# FPGA_Config_Power.net
KiCad netlist of a schematic drawn in Altium Designer
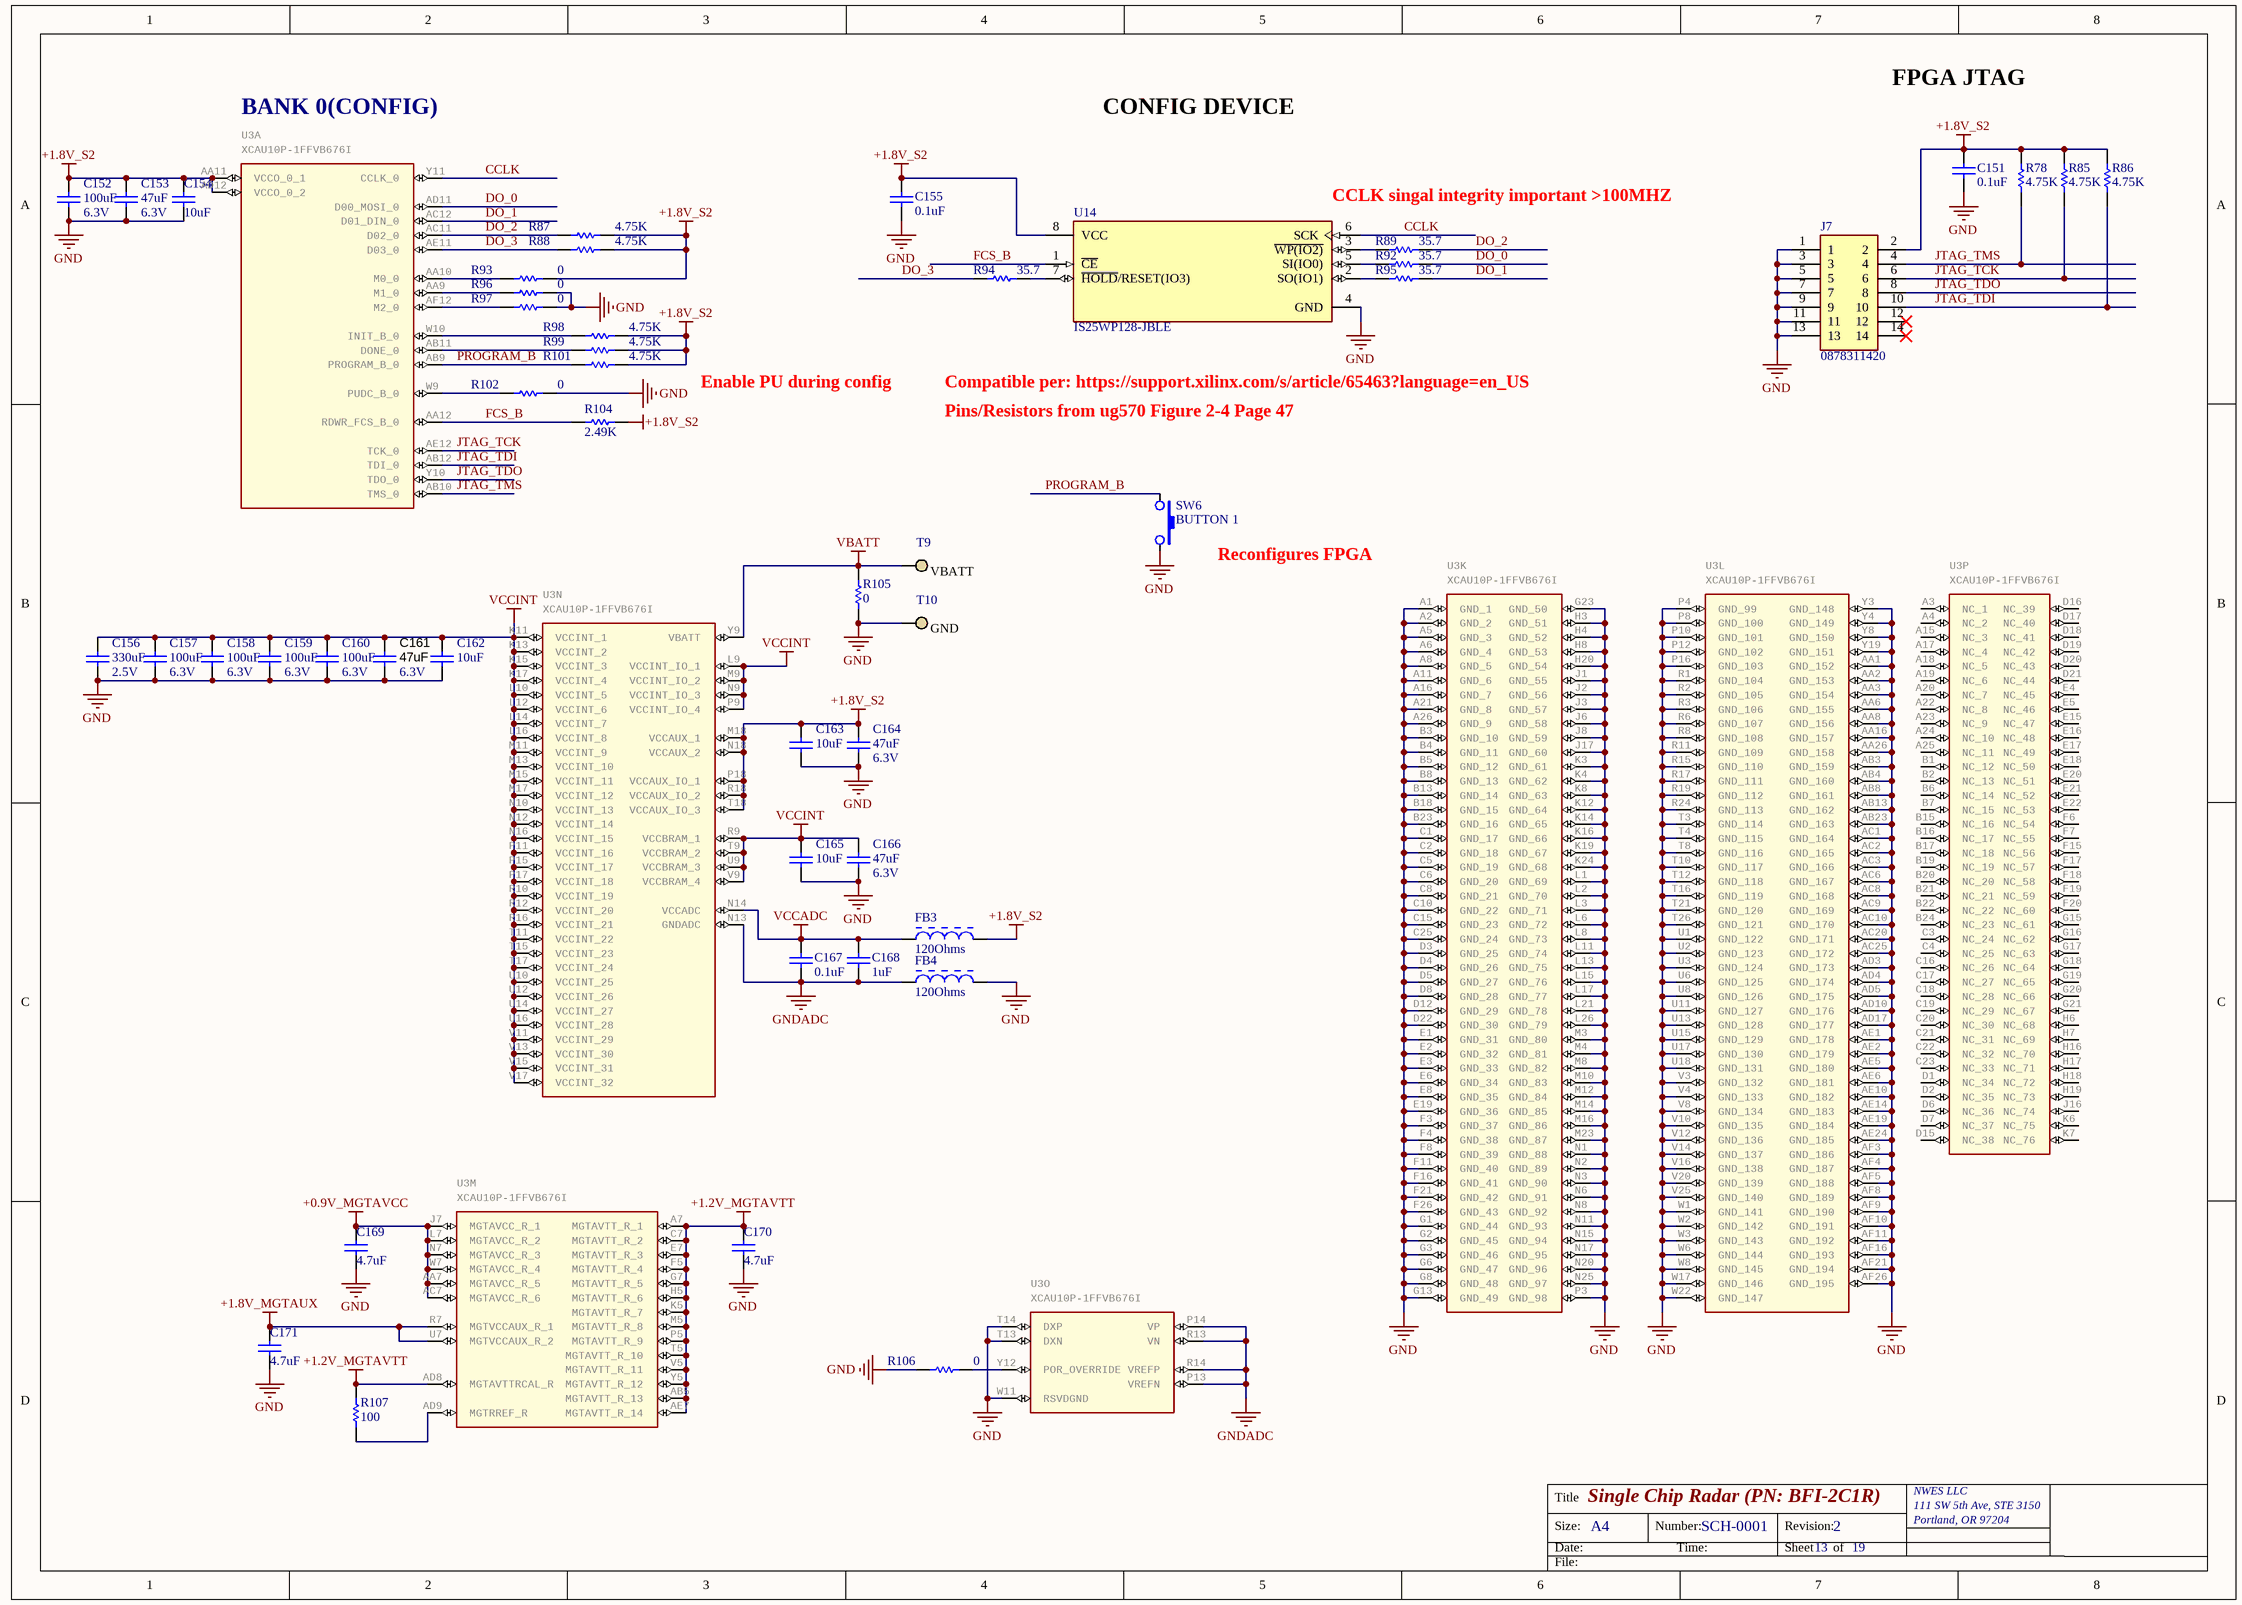
[diagram p0: FPGA Config_Power.SchDoc]

(export (version "E")
  (design (tool "Eeschema 10.0.6"))
  (components
    (comp (ref "C151")
      (value "0.1uF")
      (footprint "CAPC1005X55USR")
      (description "CAP CER 0.1UF 25V X5R 0402")
      (fields
        (field (name "MANUFACTURER PART NUMBER") "CL05A104KA5NNNC")
        (field (name "MANUFACTURER") "Samsung Electro-Mechanics")
      )
      (libsource (lib "Radar FPGA RF") (part "CAP CER 0.1UF 25V X5R 0402"))
    )
    (comp (ref "C152")
      (value "100uF")
      (footprint "CAPC2012X145USR")
      (description "0805 100 uF 6.3 V ±20% Tolerance X5R Multilayer Ceramic Chip Capacitor")
      (fields
        (field (name "MANUFACTURER") "Murata")
        (field (name "MANUFACTURER PART NUMBER") "GRM21BR60J107ME15L")
        (field (name "VOLTAGE RATING") "6.3V")
      )
      (libsource (lib "Radar FPGA RF") (part "CAP CER 100UF 6.3V X5R 0805"))
    )
    (comp (ref "C153")
      (value "47uF")
      (footprint "CAPC2012X145USR")
      (description "CAP CER 47UF 6.3V X5R 0805")
      (fields
        (field (name "MANUFACTURER") "Samsung")
        (field (name "MANUFACTURER PART NUMBER") "CL21A476MQYNNNE")
        (field (name "VOLTAGE RATING") "6.3V")
      )
      (libsource (lib "Radar FPGA RF") (part "CAP CER 47UF 6.3V X5R 0805"))
    )
    (comp (ref "C154")
      (value "10uF")
      (footprint "CAPC1005X90")
      (description "CAP CER 10UF 10V X5R 0402")
      (fields
        (field (name "MANUFACTURER PART NUMBER") "CL05A106MP8NUB8")
        (field (name "MANUFACTURER") "Samsung Electro-Mechanics")
      )
      (libsource (lib "Radar FPGA RF") (part "CAP CER 10UF 10V X5R 0402"))
    )
    (comp (ref "C155")
      (value "0.1uF")
      (footprint "CAPC1005X55USR")
      (description "CAP CER 0.1UF 25V X5R 0402")
      (fields
        (field (name "MANUFACTURER PART NUMBER") "CL05A104KA5NNNC")
        (field (name "MANUFACTURER") "Samsung Electro-Mechanics")
      )
      (libsource (lib "Radar FPGA RF") (part "CAP CER 0.1UF 25V X5R 0402"))
    )
    (comp (ref "C156")
      (value "330uF")
      (footprint "CAPC3225X280N")
      (description "1210 2.5V X6S 330uF 20% multilayer ceramic capacitor")
      (fields
        (field (name "MANUFACTURER") "Murata")
        (field (name "MANUFACTURER PART NUMBER") "GRM32EC80E337ME05L")
        (field (name "VOLTAGE RATING") "2.5V")
      )
      (libsource (lib "Radar FPGA RF") (part "CAP CER 330UF 2.5V X6S 1210"))
    )
    (comp (ref "C157")
      (value "100uF")
      (footprint "CAPC2012X145USR")
      (description "0805 100 uF 6.3 V ±20% Tolerance X5R Multilayer Ceramic Chip Capacitor")
      (fields
        (field (name "MANUFACTURER") "Murata")
        (field (name "MANUFACTURER PART NUMBER") "GRM21BR60J107ME15L")
        (field (name "VOLTAGE RATING") "6.3V")
      )
      (libsource (lib "Radar FPGA RF") (part "CAP CER 100UF 6.3V X5R 0805"))
    )
    (comp (ref "C158")
      (value "100uF")
      (footprint "CAPC2012X145USR")
      (description "0805 100 uF 6.3 V ±20% Tolerance X5R Multilayer Ceramic Chip Capacitor")
      (fields
        (field (name "MANUFACTURER") "Murata")
        (field (name "MANUFACTURER PART NUMBER") "GRM21BR60J107ME15L")
        (field (name "VOLTAGE RATING") "6.3V")
      )
      (libsource (lib "Radar FPGA RF") (part "CAP CER 100UF 6.3V X5R 0805"))
    )
    (comp (ref "C159")
      (value "100uF")
      (footprint "CAPC2012X145USR")
      (description "0805 100 uF 6.3 V ±20% Tolerance X5R Multilayer Ceramic Chip Capacitor")
      (fields
        (field (name "MANUFACTURER") "Murata")
        (field (name "MANUFACTURER PART NUMBER") "GRM21BR60J107ME15L")
        (field (name "VOLTAGE RATING") "6.3V")
      )
      (libsource (lib "Radar FPGA RF") (part "CAP CER 100UF 6.3V X5R 0805"))
    )
    (comp (ref "C160")
      (value "100uF")
      (footprint "CAPC2012X145USR")
      (description "0805 100 uF 6.3 V ±20% Tolerance X5R Multilayer Ceramic Chip Capacitor")
      (fields
        (field (name "MANUFACTURER") "Murata")
        (field (name "MANUFACTURER PART NUMBER") "GRM21BR60J107ME15L")
        (field (name "VOLTAGE RATING") "6.3V")
      )
      (libsource (lib "Radar FPGA RF") (part "CAP CER 100UF 6.3V X5R 0805"))
    )
    (comp (ref "C161")
      (value "47uF")
      (footprint "CAPC1608X100N")
      (description "0603 6.3 V 47 uF ±20% Tolerance X5R SMT Multilayer Ceramic Chp Capacitor")
      (fields
        (field (name "MANUFACTURER") "Murata")
        (field (name "MANUFACTURER PART NUMBER") "GRM188R60J476ME15D")
        (field (name "VOLTAGE RATING") "6.3V")
      )
      (libsource (lib "Radar FPGA RF") (part "CAP CER 47UF 6.3V X5R 0603"))
    )
    (comp (ref "C162")
      (value "10uF")
      (footprint "CAPC1005X90")
      (description "CAP CER 10UF 10V X5R 0402")
      (fields
        (field (name "MANUFACTURER PART NUMBER") "CL05A106MP8NUB8")
        (field (name "MANUFACTURER") "Samsung Electro-Mechanics")
      )
      (libsource (lib "Radar FPGA RF") (part "CAP CER 10UF 10V X5R 0402"))
    )
    (comp (ref "C163")
      (value "10uF")
      (footprint "CAPC1005X90")
      (description "CAP CER 10UF 10V X5R 0402")
      (fields
        (field (name "MANUFACTURER PART NUMBER") "CL05A106MP8NUB8")
        (field (name "MANUFACTURER") "Samsung Electro-Mechanics")
      )
      (libsource (lib "Radar FPGA RF") (part "CAP CER 10UF 10V X5R 0402"))
    )
    (comp (ref "C164")
      (value "47uF")
      (footprint "CAPC2012X145USR")
      (description "CAP CER 47UF 6.3V X5R 0805")
      (fields
        (field (name "MANUFACTURER") "Samsung")
        (field (name "MANUFACTURER PART NUMBER") "CL21A476MQYNNNE")
        (field (name "VOLTAGE RATING") "6.3V")
      )
      (libsource (lib "Radar FPGA RF") (part "CAP CER 47UF 6.3V X5R 0805"))
    )
    (comp (ref "C165")
      (value "10uF")
      (footprint "CAPC1005X90")
      (description "CAP CER 10UF 10V X5R 0402")
      (fields
        (field (name "MANUFACTURER PART NUMBER") "CL05A106MP8NUB8")
        (field (name "MANUFACTURER") "Samsung Electro-Mechanics")
      )
      (libsource (lib "Radar FPGA RF") (part "CAP CER 10UF 10V X5R 0402"))
    )
    (comp (ref "C166")
      (value "47uF")
      (footprint "CAPC2012X145USR")
      (description "CAP CER 47UF 6.3V X5R 0805")
      (fields
        (field (name "MANUFACTURER") "Samsung")
        (field (name "MANUFACTURER PART NUMBER") "CL21A476MQYNNNE")
        (field (name "VOLTAGE RATING") "6.3V")
      )
      (libsource (lib "Radar FPGA RF") (part "CAP CER 47UF 6.3V X5R 0805"))
    )
    (comp (ref "C167")
      (value "0.1uF")
      (footprint "CAPC1005X55USR")
      (description "CAP CER 0.1UF 25V X5R 0402")
      (fields
        (field (name "MANUFACTURER PART NUMBER") "CL05A104KA5NNNC")
        (field (name "MANUFACTURER") "Samsung Electro-Mechanics")
      )
      (libsource (lib "Radar FPGA RF") (part "CAP CER 0.1UF 25V X5R 0402"))
    )
    (comp (ref "C168")
      (value "1uF")
      (footprint "CAPC1005X55USR")
      (description "CAP CER 1UF 25V X5R 0402")
      (fields
        (field (name "MANUFACTURER PART NUMBER") "GRM155R61E105MA12D")
        (field (name "MANUFACTURER") "Murata Electronics")
      )
      (libsource (lib "Radar FPGA RF") (part "CAP CER 1UF 25V X5R 0402"))
    )
    (comp (ref "C169")
      (value "4.7uF")
      (footprint "CAPC1005X65USR")
      (description "CAP CER 4.7UF 10V X5R 0402")
      (fields
        (field (name "MANUFACTURER PART NUMBER") "C1005X5R1A475M050BC")
        (field (name "MANUFACTURER") "TDK Corporation")
      )
      (libsource (lib "Radar FPGA RF") (part "CAP CER 4.7UF 10V X5R 0402"))
    )
    (comp (ref "C170")
      (value "4.7uF")
      (footprint "CAPC1005X65USR")
      (description "CAP CER 4.7UF 10V X5R 0402")
      (fields
        (field (name "MANUFACTURER PART NUMBER") "C1005X5R1A475M050BC")
        (field (name "MANUFACTURER") "TDK Corporation")
      )
      (libsource (lib "Radar FPGA RF") (part "CAP CER 4.7UF 10V X5R 0402"))
    )
    (comp (ref "C171")
      (value "4.7uF")
      (footprint "CAPC1005X65USR")
      (description "CAP CER 4.7UF 10V X5R 0402")
      (fields
        (field (name "MANUFACTURER PART NUMBER") "C1005X5R1A475M050BC")
        (field (name "MANUFACTURER") "TDK Corporation")
      )
      (libsource (lib "Radar FPGA RF") (part "CAP CER 4.7UF 10V X5R 0402"))
    )
    (comp (ref "FB3")
      (value "120Ohms")
      (footprint "0402_FB")
      (description "FERRITE BEAD 120 OHM 0402 1LN")
      (fields
        (field (name "MANUFACTURER PART NUMBER") "BLM15AG121SN1D")
        (field (name "MANUFACTURER") "Murata Electronics")
      )
      (libsource (lib "Radar FPGA RF") (part "FERRITE BEAD 120 OHM 0402 1LN"))
    )
    (comp (ref "FB4")
      (value "120Ohms")
      (footprint "0402_FB")
      (description "FERRITE BEAD 120 OHM 0402 1LN")
      (fields
        (field (name "MANUFACTURER PART NUMBER") "BLM15AG121SN1D")
        (field (name "MANUFACTURER") "Murata Electronics")
      )
      (libsource (lib "Radar FPGA RF") (part "FERRITE BEAD 120 OHM 0402 1LN"))
    )
    (comp (ref "J7")
      (value "0878311420")
      (footprint "Molex_0878311420")
      (description "2.00mm Pitch Milli-Grid Header Vertical Through Hole Shrouded 14 Circuits 0.38")
      (fields (field (name "MANUFACTURER") "Molex") (field (name "MANUFACTURER PART NUMBER") "87831-1420"))
      (libsource (lib "Radar FPGA RF") (part "HEADER VERT 2X7 2MM"))
    )
    (comp (ref "R78")
      (value "4.75K")
      (footprint "RESC1005X40USR")
      (description "RES 4.75K OHM 1% 1/16W 0402")
      (fields
        (field (name "MANUFACTURER") "YAGEO")
        (field (name "MANUFACTURER PART NUMBER") "RC0402FR-074K75L")
      )
      (libsource (lib "Radar FPGA RF") (part "RES 4.75K OHM 1% 1/16W 0402"))
    )
    (comp (ref "R85")
      (value "4.75K")
      (footprint "RESC1005X40USR")
      (description "RES 4.75K OHM 1% 1/16W 0402")
      (fields
        (field (name "MANUFACTURER") "YAGEO")
        (field (name "MANUFACTURER PART NUMBER") "RC0402FR-074K75L")
      )
      (libsource (lib "Radar FPGA RF") (part "RES 4.75K OHM 1% 1/16W 0402"))
    )
    (comp (ref "R86")
      (value "4.75K")
      (footprint "RESC1005X40USR")
      (description "RES 4.75K OHM 1% 1/16W 0402")
      (fields
        (field (name "MANUFACTURER") "YAGEO")
        (field (name "MANUFACTURER PART NUMBER") "RC0402FR-074K75L")
      )
      (libsource (lib "Radar FPGA RF") (part "RES 4.75K OHM 1% 1/16W 0402"))
    )
    (comp (ref "R87")
      (value "4.75K")
      (footprint "RESC1005X40USR")
      (description "RES 4.75K OHM 1% 1/16W 0402")
      (fields
        (field (name "MANUFACTURER") "YAGEO")
        (field (name "MANUFACTURER PART NUMBER") "RC0402FR-074K75L")
      )
      (libsource (lib "Radar FPGA RF") (part "RES 4.75K OHM 1% 1/16W 0402"))
    )
    (comp (ref "R88")
      (value "4.75K")
      (footprint "RESC1005X40USR")
      (description "RES 4.75K OHM 1% 1/16W 0402")
      (fields
        (field (name "MANUFACTURER") "YAGEO")
        (field (name "MANUFACTURER PART NUMBER") "RC0402FR-074K75L")
      )
      (libsource (lib "Radar FPGA RF") (part "RES 4.75K OHM 1% 1/16W 0402"))
    )
    (comp (ref "R89")
      (value "35.7")
      (footprint "RESC1005X40USR")
      (description "RES 35.7 OHM 1% 1/16W 0402")
      (fields
        (field (name "MANUFACTURER") "YAGEO")
        (field (name "MANUFACTURER PART NUMBER") "RC0402FR-0735R7L")
      )
      (libsource (lib "Radar FPGA RF") (part "RES 35.7 OHM 1% 1/16W 0402"))
    )
    (comp (ref "R92")
      (value "35.7")
      (footprint "RESC1005X40USR")
      (description "RES 35.7 OHM 1% 1/16W 0402")
      (fields
        (field (name "MANUFACTURER") "YAGEO")
        (field (name "MANUFACTURER PART NUMBER") "RC0402FR-0735R7L")
      )
      (libsource (lib "Radar FPGA RF") (part "RES 35.7 OHM 1% 1/16W 0402"))
    )
    (comp (ref "R93")
      (value "0")
      (footprint "RESC1005X40USR")
      (description "RES 0 OHM JUMPER 1/16W 0402")
      (fields
        (field (name "MANUFACTURER") "Yageo")
        (field (name "MANUFACTURER PART NUMBER") "RC0402JR-070RL")
      )
      (libsource (lib "Radar FPGA RF") (part "RES 0 OHM JUMPER 1/16W 0402"))
    )
    (comp (ref "R94")
      (value "35.7")
      (footprint "RESC1005X40USR")
      (description "RES 35.7 OHM 1% 1/16W 0402")
      (fields
        (field (name "MANUFACTURER") "YAGEO")
        (field (name "MANUFACTURER PART NUMBER") "RC0402FR-0735R7L")
      )
      (libsource (lib "Radar FPGA RF") (part "RES 35.7 OHM 1% 1/16W 0402"))
    )
    (comp (ref "R95")
      (value "35.7")
      (footprint "RESC1005X40USR")
      (description "RES 35.7 OHM 1% 1/16W 0402")
      (fields
        (field (name "MANUFACTURER") "YAGEO")
        (field (name "MANUFACTURER PART NUMBER") "RC0402FR-0735R7L")
      )
      (libsource (lib "Radar FPGA RF") (part "RES 35.7 OHM 1% 1/16W 0402"))
    )
    (comp (ref "R96")
      (value "0")
      (footprint "RESC1005X40USR")
      (description "RES 0 OHM JUMPER 1/16W 0402")
      (fields
        (field (name "MANUFACTURER") "Yageo")
        (field (name "MANUFACTURER PART NUMBER") "RC0402JR-070RL")
      )
      (libsource (lib "Radar FPGA RF") (part "RES 0 OHM JUMPER 1/16W 0402"))
    )
    (comp (ref "R97")
      (value "0")
      (footprint "RESC1005X40USR")
      (description "RES 0 OHM JUMPER 1/16W 0402")
      (fields
        (field (name "MANUFACTURER") "Yageo")
        (field (name "MANUFACTURER PART NUMBER") "RC0402JR-070RL")
      )
      (libsource (lib "Radar FPGA RF") (part "RES 0 OHM JUMPER 1/16W 0402"))
    )
    (comp (ref "R98")
      (value "4.75K")
      (footprint "RESC1005X40USR")
      (description "RES 4.75K OHM 1% 1/16W 0402")
      (fields
        (field (name "MANUFACTURER") "YAGEO")
        (field (name "MANUFACTURER PART NUMBER") "RC0402FR-074K75L")
      )
      (libsource (lib "Radar FPGA RF") (part "RES 4.75K OHM 1% 1/16W 0402"))
    )
    (comp (ref "R99")
      (value "4.75K")
      (footprint "RESC1005X40USR")
      (description "RES 4.75K OHM 1% 1/16W 0402")
      (fields
        (field (name "MANUFACTURER") "YAGEO")
        (field (name "MANUFACTURER PART NUMBER") "RC0402FR-074K75L")
      )
      (libsource (lib "Radar FPGA RF") (part "RES 4.75K OHM 1% 1/16W 0402"))
    )
    (comp (ref "R101")
      (value "4.75K")
      (footprint "RESC1005X40USR")
      (description "RES 4.75K OHM 1% 1/16W 0402")
      (fields
        (field (name "MANUFACTURER") "YAGEO")
        (field (name "MANUFACTURER PART NUMBER") "RC0402FR-074K75L")
      )
      (libsource (lib "Radar FPGA RF") (part "RES 4.75K OHM 1% 1/16W 0402"))
    )
    (comp (ref "R102")
      (value "0")
      (footprint "RESC1005X40USR")
      (description "RES 0 OHM JUMPER 1/16W 0402")
      (fields
        (field (name "MANUFACTURER") "Yageo")
        (field (name "MANUFACTURER PART NUMBER") "RC0402JR-070RL")
      )
      (libsource (lib "Radar FPGA RF") (part "RES 0 OHM JUMPER 1/16W 0402"))
    )
    (comp (ref "R104")
      (value "2.49K")
      (footprint "RESC1005X40USR")
      (description "RES 2.49K OHM 1% 1/16W 0402")
      (fields
        (field (name "MANUFACTURER") "YAGEO")
        (field (name "MANUFACTURER PART NUMBER") "RC0402FR-072K49L")
      )
      (libsource (lib "Radar FPGA RF") (part "RES 2.49K OHM 1% 1/16W 0402"))
    )
    (comp (ref "R105")
      (value "0")
      (footprint "RESC1005X40USR")
      (description "RES 0 OHM JUMPER 1/16W 0402")
      (fields
        (field (name "MANUFACTURER") "Yageo")
        (field (name "MANUFACTURER PART NUMBER") "RC0402JR-070RL")
      )
      (libsource (lib "Radar FPGA RF") (part "RES 0 OHM JUMPER 1/16W 0402"))
    )
    (comp (ref "R106")
      (value "0")
      (footprint "RESC1005X40USR")
      (description "RES 0 OHM JUMPER 1/16W 0402")
      (fields
        (field (name "MANUFACTURER") "Yageo")
        (field (name "MANUFACTURER PART NUMBER") "RC0402JR-070RL")
      )
      (libsource (lib "Radar FPGA RF") (part "RES 0 OHM JUMPER 1/16W 0402"))
    )
    (comp (ref "R107")
      (value "100")
      (footprint "RESC1005X40USR")
      (description "RES 100 OHM 1% 1/16W 0402")
      (fields
        (field (name "MANUFACTURER") "YAGEO")
        (field (name "MANUFACTURER PART NUMBER") "RC0402FR-07100RL")
      )
      (libsource (lib "Radar FPGA RF") (part "RES 100 OHM 1% 1/16W 0402"))
    )
    (comp (ref "SW6")
      (value "BUTTON 1")
      (footprint "PTS820J25MSMTRLFS")
      (description "C&K Series-PTS Tactile Switch PTS820 J25K SMTR LFS")
      (fields
        (field (name "MANUFACTURER") "ITT C&K")
        (field (name "MANUFACTURER PART NUMBER") "PTS820J25KSMTRLFS")
      )
      (libsource (lib "Radar FPGA RF") (part "SW_PTS820"))
    )
    (comp (ref "T9")
      (value "TP_S")
      (footprint "TP_SM_1MM")
      (description "test point")
      (fields (field (name "PARAMETER 1") "VBATT"))
      (libsource (lib "Radar FPGA RF") (part "Test point PAD"))
    )
    (comp (ref "T10")
      (value "TP_S")
      (footprint "TP_SM_1MM")
      (description "test point")
      (fields (field (name "PARAMETER 1") "GND"))
      (libsource (lib "Radar FPGA RF") (part "Test point PAD"))
    )
    (comp (ref "U3")
      (value "XCAU10P-1FFVB676I")
      (footprint "676-FCBGA (27x27)")
      (description "IC FPGA ARTIXUP 676BGA")
      (fields (field (name "MANUFACTURER") "AMD Xilinx"))
      (libsource (lib "LL") (part "XCAU10P-1FFVB676I"))
    )
    (comp (ref "U14")
      (value "IS25WP128-JBLE")
      (footprint "SOIC8_5.3mm_W")
      (description "128M QPI/QSPI, 8- SOP 208M , R HS, ET")
      (fields (field (name "MANUFACTURER") "ISSI"))
      (libsource (lib "Radar FPGA RF") (part "IS25WP128-JBLE"))
    )
  )
  (nets
    (net (code "1") (name "+0.9V_MGTAVCC") (class "Default")
      (node (ref "C169") (pin "2") (pinfunction "2_2") (pintype "passive"))
      (node (ref "U3") (pin "AA7") (pinfunction "MGTAVCC_R_5_AA7") (pintype "bidirectional"))
      (node (ref "U3") (pin "AC7") (pinfunction "MGTAVCC_R_6_AC7") (pintype "bidirectional"))
      (node (ref "U3") (pin "J7") (pinfunction "MGTAVCC_R_1_J7") (pintype "bidirectional"))
      (node (ref "U3") (pin "L7") (pinfunction "MGTAVCC_R_2_L7") (pintype "bidirectional"))
      (node (ref "U3") (pin "N7") (pinfunction "MGTAVCC_R_3_N7") (pintype "bidirectional"))
      (node (ref "U3") (pin "W7") (pinfunction "MGTAVCC_R_4_W7") (pintype "bidirectional"))
    )
    (net (code "2") (name "+1.2V_MGTAVTT") (class "Default")
      (node (ref "C170") (pin "2") (pinfunction "2_2") (pintype "passive"))
      (node (ref "R107") (pin "2") (pinfunction "2_2") (pintype "passive"))
      (node (ref "U3") (pin "A7") (pinfunction "MGTAVTT_R_1_A7") (pintype "bidirectional"))
      (node (ref "U3") (pin "AB5") (pinfunction "MGTAVTT_R_13_AB5") (pintype "bidirectional"))
      (node (ref "U3") (pin "AD8") (pinfunction "MGTAVTTRCAL_R_AD8") (pintype "bidirectional"))
      (node (ref "U3") (pin "AE7") (pinfunction "MGTAVTT_R_14_AE7") (pintype "bidirectional"))
      (node (ref "U3") (pin "C7") (pinfunction "MGTAVTT_R_2_C7") (pintype "bidirectional"))
      (node (ref "U3") (pin "E7") (pinfunction "MGTAVTT_R_3_E7") (pintype "bidirectional"))
      (node (ref "U3") (pin "F5") (pinfunction "MGTAVTT_R_4_F5") (pintype "bidirectional"))
      (node (ref "U3") (pin "G7") (pinfunction "MGTAVTT_R_5_G7") (pintype "bidirectional"))
      (node (ref "U3") (pin "H5") (pinfunction "MGTAVTT_R_6_H5") (pintype "bidirectional"))
      (node (ref "U3") (pin "K5") (pinfunction "MGTAVTT_R_7_K5") (pintype "bidirectional"))
      (node (ref "U3") (pin "M5") (pinfunction "MGTAVTT_R_8_M5") (pintype "bidirectional"))
      (node (ref "U3") (pin "P5") (pinfunction "MGTAVTT_R_9_P5") (pintype "bidirectional"))
      (node (ref "U3") (pin "T5") (pinfunction "MGTAVTT_R_10_T5") (pintype "bidirectional"))
      (node (ref "U3") (pin "V5") (pinfunction "MGTAVTT_R_11_V5") (pintype "bidirectional"))
      (node (ref "U3") (pin "Y5") (pinfunction "MGTAVTT_R_12_Y5") (pintype "bidirectional"))
    )
    (net (code "3") (name "+1.8V_MGTAUX") (class "Default")
      (node (ref "C171") (pin "2") (pinfunction "2_2") (pintype "passive"))
      (node (ref "U3") (pin "R7") (pinfunction "MGTVCCAUX_R_1_R7") (pintype "bidirectional"))
      (node (ref "U3") (pin "U7") (pinfunction "MGTVCCAUX_R_2_U7") (pintype "bidirectional"))
    )
    (net (code "4") (name "+1.8V_S2") (class "Default")
      (node (ref "C151") (pin "2") (pinfunction "2_2") (pintype "passive"))
      (node (ref "C152") (pin "1") (pinfunction "1_1") (pintype "passive"))
      (node (ref "C153") (pin "1") (pinfunction "1_1") (pintype "passive"))
      (node (ref "C154") (pin "2") (pinfunction "2_2") (pintype "passive"))
      (node (ref "C155") (pin "2") (pinfunction "2_2") (pintype "passive"))
      (node (ref "C163") (pin "2") (pinfunction "2_2") (pintype "passive"))
      (node (ref "C164") (pin "1") (pinfunction "1_1") (pintype "passive"))
      (node (ref "FB3") (pin "2") (pinfunction "2_2") (pintype "passive"))
      (node (ref "J7") (pin "2") (pinfunction "2_2") (pintype "passive"))
      (node (ref "R101") (pin "1") (pinfunction "1_1") (pintype "passive"))
      (node (ref "R104") (pin "1") (pinfunction "1_1") (pintype "passive"))
      (node (ref "R78") (pin "2") (pinfunction "2_2") (pintype "passive"))
      (node (ref "R85") (pin "2") (pinfunction "2_2") (pintype "passive"))
      (node (ref "R86") (pin "2") (pinfunction "2_2") (pintype "passive"))
      (node (ref "R87") (pin "1") (pinfunction "1_1") (pintype "passive"))
      (node (ref "R88") (pin "1") (pinfunction "1_1") (pintype "passive"))
      (node (ref "R93") (pin "2") (pinfunction "2_2") (pintype "passive"))
      (node (ref "R98") (pin "1") (pinfunction "1_1") (pintype "passive"))
      (node (ref "R99") (pin "1") (pinfunction "1_1") (pintype "passive"))
      (node (ref "U14") (pin "8") (pinfunction "VCC_8") (pintype "power_in"))
      (node (ref "U3") (pin "AA11") (pinfunction "VCCO_0_1_AA11") (pintype "bidirectional"))
      (node (ref "U3") (pin "AD12") (pinfunction "VCCO_0_2_AD12") (pintype "bidirectional"))
      (node (ref "U3") (pin "M18") (pinfunction "VCCAUX_1_M18") (pintype "bidirectional"))
      (node (ref "U3") (pin "N18") (pinfunction "VCCAUX_2_N18") (pintype "bidirectional"))
      (node (ref "U3") (pin "P18") (pinfunction "VCCAUX_IO_1_P18") (pintype "bidirectional"))
      (node (ref "U3") (pin "R18") (pinfunction "VCCAUX_IO_2_R18") (pintype "bidirectional"))
      (node (ref "U3") (pin "T18") (pinfunction "VCCAUX_IO_3_T18") (pintype "bidirectional"))
    )
    (net (code "5") (name "/CCLK") (class "Default")
      (node (ref "U14") (pin "6") (pinfunction "SCK_6") (pintype "input"))
      (node (ref "U3") (pin "Y11") (pinfunction "CCLK_0_Y11") (pintype "bidirectional"))
    )
    (net (code "6") (name "/DO_0") (class "Default")
      (node (ref "R92") (pin "1") (pinfunction "1_1") (pintype "passive"))
      (node (ref "U3") (pin "AD11") (pinfunction "D00_MOSI_0_AD11") (pintype "bidirectional"))
    )
    (net (code "7") (name "/DO_1") (class "Default")
      (node (ref "R95") (pin "1") (pinfunction "1_1") (pintype "passive"))
      (node (ref "U3") (pin "AC12") (pinfunction "D01_DIN_0_AC12") (pintype "bidirectional"))
    )
    (net (code "8") (name "/DO_2") (class "Default")
      (node (ref "R87") (pin "2") (pinfunction "2_2") (pintype "passive"))
      (node (ref "R89") (pin "1") (pinfunction "1_1") (pintype "passive"))
      (node (ref "U3") (pin "AC11") (pinfunction "D02_0_AC11") (pintype "bidirectional"))
    )
    (net (code "9") (name "/DO_3") (class "Default")
      (node (ref "R88") (pin "2") (pinfunction "2_2") (pintype "passive"))
      (node (ref "R94") (pin "2") (pinfunction "2_2") (pintype "passive"))
      (node (ref "U3") (pin "AE11") (pinfunction "D03_0_AE11") (pintype "bidirectional"))
    )
    (net (code "10") (name "/FCS_B") (class "Default")
      (node (ref "R104") (pin "2") (pinfunction "2_2") (pintype "passive"))
      (node (ref "U14") (pin "1") (pinfunction "~{CE}_1") (pintype "input"))
      (node (ref "U3") (pin "AA12") (pinfunction "RDWR_FCS_B_0_AA12") (pintype "bidirectional"))
    )
    (net (code "11") (name "/JTAG_TCK") (class "Default")
      (node (ref "J7") (pin "6") (pinfunction "6_6") (pintype "passive"))
      (node (ref "R85") (pin "1") (pinfunction "1_1") (pintype "passive"))
      (node (ref "U3") (pin "AE12") (pinfunction "TCK_0_AE12") (pintype "bidirectional"))
    )
    (net (code "12") (name "/JTAG_TDI") (class "Default")
      (node (ref "J7") (pin "10") (pinfunction "10_10") (pintype "passive"))
      (node (ref "R86") (pin "1") (pinfunction "1_1") (pintype "passive"))
      (node (ref "U3") (pin "AB12") (pinfunction "TDI_0_AB12") (pintype "bidirectional"))
    )
    (net (code "13") (name "/JTAG_TDO") (class "Default")
      (node (ref "J7") (pin "8") (pinfunction "8_8") (pintype "passive"))
      (node (ref "U3") (pin "Y10") (pinfunction "TDO_0_Y10") (pintype "bidirectional"))
    )
    (net (code "14") (name "/JTAG_TMS") (class "Default")
      (node (ref "J7") (pin "4") (pinfunction "4_4") (pintype "passive"))
      (node (ref "R78") (pin "1") (pinfunction "1_1") (pintype "passive"))
      (node (ref "U3") (pin "AB10") (pinfunction "TMS_0_AB10") (pintype "bidirectional"))
    )
    (net (code "15") (name "/PROGRAM_B") (class "Default")
      (node (ref "R101") (pin "2") (pinfunction "2_2") (pintype "passive"))
      (node (ref "SW6") (pin "1") (pinfunction "1_1") (pintype "passive"))
      (node (ref "U3") (pin "AB9") (pinfunction "PROGRAM_B_0_AB9") (pintype "bidirectional"))
    )
    (net (code "16") (name "GND") (class "Default")
      (node (ref "C151") (pin "1") (pinfunction "1_1") (pintype "passive"))
      (node (ref "C152") (pin "2") (pinfunction "2_2") (pintype "passive"))
      (node (ref "C153") (pin "2") (pinfunction "2_2") (pintype "passive"))
      (node (ref "C154") (pin "1") (pinfunction "1_1") (pintype "passive"))
      (node (ref "C155") (pin "1") (pinfunction "1_1") (pintype "passive"))
      (node (ref "C156") (pin "2") (pinfunction "2_2") (pintype "passive"))
      (node (ref "C157") (pin "2") (pinfunction "2_2") (pintype "passive"))
      (node (ref "C158") (pin "2") (pinfunction "2_2") (pintype "passive"))
      (node (ref "C159") (pin "2") (pinfunction "2_2") (pintype "passive"))
      (node (ref "C160") (pin "2") (pinfunction "2_2") (pintype "passive"))
      (node (ref "C161") (pin "2") (pinfunction "2_2") (pintype "passive"))
      (node (ref "C162") (pin "1") (pinfunction "1_1") (pintype "passive"))
      (node (ref "C163") (pin "1") (pinfunction "1_1") (pintype "passive"))
      (node (ref "C164") (pin "2") (pinfunction "2_2") (pintype "passive"))
      (node (ref "C165") (pin "1") (pinfunction "1_1") (pintype "passive"))
      (node (ref "C166") (pin "2") (pinfunction "2_2") (pintype "passive"))
      (node (ref "C169") (pin "1") (pinfunction "1_1") (pintype "passive"))
      (node (ref "C170") (pin "1") (pinfunction "1_1") (pintype "passive"))
      (node (ref "C171") (pin "1") (pinfunction "1_1") (pintype "passive"))
      (node (ref "FB4") (pin "2") (pinfunction "2_2") (pintype "passive"))
      (node (ref "J7") (pin "1") (pinfunction "1_1") (pintype "passive"))
      (node (ref "J7") (pin "11") (pinfunction "11_11") (pintype "passive"))
      (node (ref "J7") (pin "13") (pinfunction "13_13") (pintype "passive"))
      (node (ref "J7") (pin "3") (pinfunction "3_3") (pintype "passive"))
      (node (ref "J7") (pin "5") (pinfunction "5_5") (pintype "passive"))
      (node (ref "J7") (pin "7") (pinfunction "7_7") (pintype "passive"))
      (node (ref "J7") (pin "9") (pinfunction "9_9") (pintype "passive"))
      (node (ref "R102") (pin "2") (pinfunction "2_2") (pintype "passive"))
      (node (ref "R105") (pin "1") (pinfunction "1_1") (pintype "passive"))
      (node (ref "R106") (pin "1") (pinfunction "1_1") (pintype "passive"))
      (node (ref "R96") (pin "2") (pinfunction "2_2") (pintype "passive"))
      (node (ref "R97") (pin "2") (pinfunction "2_2") (pintype "passive"))
      (node (ref "SW6") (pin "2") (pinfunction "2_2") (pintype "passive"))
      (node (ref "T10") (pin "1") (pintype "passive"))
      (node (ref "U14") (pin "4") (pinfunction "GND_4") (pintype "power_in"))
      (node (ref "U3") (pin "A1") (pinfunction "GND_1_A1") (pintype "bidirectional"))
      (node (ref "U3") (pin "A11") (pinfunction "GND_6_A11") (pintype "bidirectional"))
      (node (ref "U3") (pin "A16") (pinfunction "GND_7_A16") (pintype "bidirectional"))
      (node (ref "U3") (pin "A2") (pinfunction "GND_2_A2") (pintype "bidirectional"))
      (node (ref "U3") (pin "A21") (pinfunction "GND_8_A21") (pintype "bidirectional"))
      (node (ref "U3") (pin "A26") (pinfunction "GND_9_A26") (pintype "bidirectional"))
      (node (ref "U3") (pin "A5") (pinfunction "GND_3_A5") (pintype "bidirectional"))
      (node (ref "U3") (pin "A6") (pinfunction "GND_4_A6") (pintype "bidirectional"))
      (node (ref "U3") (pin "A8") (pinfunction "GND_5_A8") (pintype "bidirectional"))
      (node (ref "U3") (pin "AA1") (pinfunction "GND_152_AA1") (pintype "bidirectional"))
      (node (ref "U3") (pin "AA16") (pinfunction "GND_157_AA16") (pintype "bidirectional"))
      (node (ref "U3") (pin "AA2") (pinfunction "GND_153_AA2") (pintype "bidirectional"))
      (node (ref "U3") (pin "AA26") (pinfunction "GND_158_AA26") (pintype "bidirectional"))
      (node (ref "U3") (pin "AA3") (pinfunction "GND_154_AA3") (pintype "bidirectional"))
      (node (ref "U3") (pin "AA6") (pinfunction "GND_155_AA6") (pintype "bidirectional"))
      (node (ref "U3") (pin "AA8") (pinfunction "GND_156_AA8") (pintype "bidirectional"))
      (node (ref "U3") (pin "AB13") (pinfunction "GND_162_AB13") (pintype "bidirectional"))
      (node (ref "U3") (pin "AB23") (pinfunction "GND_163_AB23") (pintype "bidirectional"))
      (node (ref "U3") (pin "AB3") (pinfunction "GND_159_AB3") (pintype "bidirectional"))
      (node (ref "U3") (pin "AB4") (pinfunction "GND_160_AB4") (pintype "bidirectional"))
      (node (ref "U3") (pin "AB8") (pinfunction "GND_161_AB8") (pintype "bidirectional"))
      (node (ref "U3") (pin "AC1") (pinfunction "GND_164_AC1") (pintype "bidirectional"))
      (node (ref "U3") (pin "AC10") (pinfunction "GND_170_AC10") (pintype "bidirectional"))
      (node (ref "U3") (pin "AC2") (pinfunction "GND_165_AC2") (pintype "bidirectional"))
      (node (ref "U3") (pin "AC20") (pinfunction "GND_171_AC20") (pintype "bidirectional"))
      (node (ref "U3") (pin "AC25") (pinfunction "GND_172_AC25") (pintype "bidirectional"))
      (node (ref "U3") (pin "AC3") (pinfunction "GND_166_AC3") (pintype "bidirectional"))
      (node (ref "U3") (pin "AC6") (pinfunction "GND_167_AC6") (pintype "bidirectional"))
      (node (ref "U3") (pin "AC8") (pinfunction "GND_168_AC8") (pintype "bidirectional"))
      (node (ref "U3") (pin "AC9") (pinfunction "GND_169_AC9") (pintype "bidirectional"))
      (node (ref "U3") (pin "AD10") (pinfunction "GND_176_AD10") (pintype "bidirectional"))
      (node (ref "U3") (pin "AD17") (pinfunction "GND_177_AD17") (pintype "bidirectional"))
      (node (ref "U3") (pin "AD3") (pinfunction "GND_173_AD3") (pintype "bidirectional"))
      (node (ref "U3") (pin "AD4") (pinfunction "GND_174_AD4") (pintype "bidirectional"))
      (node (ref "U3") (pin "AD5") (pinfunction "GND_175_AD5") (pintype "bidirectional"))
      (node (ref "U3") (pin "AE1") (pinfunction "GND_178_AE1") (pintype "bidirectional"))
      (node (ref "U3") (pin "AE10") (pinfunction "GND_182_AE10") (pintype "bidirectional"))
      (node (ref "U3") (pin "AE14") (pinfunction "GND_183_AE14") (pintype "bidirectional"))
      (node (ref "U3") (pin "AE19") (pinfunction "GND_184_AE19") (pintype "bidirectional"))
      (node (ref "U3") (pin "AE2") (pinfunction "GND_179_AE2") (pintype "bidirectional"))
      (node (ref "U3") (pin "AE24") (pinfunction "GND_185_AE24") (pintype "bidirectional"))
      (node (ref "U3") (pin "AE5") (pinfunction "GND_180_AE5") (pintype "bidirectional"))
      (node (ref "U3") (pin "AE6") (pinfunction "GND_181_AE6") (pintype "bidirectional"))
      (node (ref "U3") (pin "AF10") (pinfunction "GND_191_AF10") (pintype "bidirectional"))
      (node (ref "U3") (pin "AF11") (pinfunction "GND_192_AF11") (pintype "bidirectional"))
      (node (ref "U3") (pin "AF16") (pinfunction "GND_193_AF16") (pintype "bidirectional"))
      (node (ref "U3") (pin "AF21") (pinfunction "GND_194_AF21") (pintype "bidirectional"))
      (node (ref "U3") (pin "AF26") (pinfunction "GND_195_AF26") (pintype "bidirectional"))
      (node (ref "U3") (pin "AF3") (pinfunction "GND_186_AF3") (pintype "bidirectional"))
      (node (ref "U3") (pin "AF4") (pinfunction "GND_187_AF4") (pintype "bidirectional"))
      (node (ref "U3") (pin "AF5") (pinfunction "GND_188_AF5") (pintype "bidirectional"))
      (node (ref "U3") (pin "AF8") (pinfunction "GND_189_AF8") (pintype "bidirectional"))
      (node (ref "U3") (pin "AF9") (pinfunction "GND_190_AF9") (pintype "bidirectional"))
      (node (ref "U3") (pin "B13") (pinfunction "GND_14_B13") (pintype "bidirectional"))
      (node (ref "U3") (pin "B18") (pinfunction "GND_15_B18") (pintype "bidirectional"))
      (node (ref "U3") (pin "B23") (pinfunction "GND_16_B23") (pintype "bidirectional"))
      (node (ref "U3") (pin "B3") (pinfunction "GND_10_B3") (pintype "bidirectional"))
      (node (ref "U3") (pin "B4") (pinfunction "GND_11_B4") (pintype "bidirectional"))
      (node (ref "U3") (pin "B5") (pinfunction "GND_12_B5") (pintype "bidirectional"))
      (node (ref "U3") (pin "B8") (pinfunction "GND_13_B8") (pintype "bidirectional"))
      (node (ref "U3") (pin "C1") (pinfunction "GND_17_C1") (pintype "bidirectional"))
      (node (ref "U3") (pin "C10") (pinfunction "GND_22_C10") (pintype "bidirectional"))
      (node (ref "U3") (pin "C15") (pinfunction "GND_23_C15") (pintype "bidirectional"))
      (node (ref "U3") (pin "C2") (pinfunction "GND_18_C2") (pintype "bidirectional"))
      (node (ref "U3") (pin "C25") (pinfunction "GND_24_C25") (pintype "bidirectional"))
      (node (ref "U3") (pin "C5") (pinfunction "GND_19_C5") (pintype "bidirectional"))
      (node (ref "U3") (pin "C6") (pinfunction "GND_20_C6") (pintype "bidirectional"))
      (node (ref "U3") (pin "C8") (pinfunction "GND_21_C8") (pintype "bidirectional"))
      (node (ref "U3") (pin "D12") (pinfunction "GND_29_D12") (pintype "bidirectional"))
      (node (ref "U3") (pin "D22") (pinfunction "GND_30_D22") (pintype "bidirectional"))
      (node (ref "U3") (pin "D3") (pinfunction "GND_25_D3") (pintype "bidirectional"))
      (node (ref "U3") (pin "D4") (pinfunction "GND_26_D4") (pintype "bidirectional"))
      (node (ref "U3") (pin "D5") (pinfunction "GND_27_D5") (pintype "bidirectional"))
      (node (ref "U3") (pin "D8") (pinfunction "GND_28_D8") (pintype "bidirectional"))
      (node (ref "U3") (pin "E1") (pinfunction "GND_31_E1") (pintype "bidirectional"))
      (node (ref "U3") (pin "E19") (pinfunction "GND_36_E19") (pintype "bidirectional"))
      (node (ref "U3") (pin "E2") (pinfunction "GND_32_E2") (pintype "bidirectional"))
      (node (ref "U3") (pin "E3") (pinfunction "GND_33_E3") (pintype "bidirectional"))
      (node (ref "U3") (pin "E6") (pinfunction "GND_34_E6") (pintype "bidirectional"))
      (node (ref "U3") (pin "E8") (pinfunction "GND_35_E8") (pintype "bidirectional"))
      (node (ref "U3") (pin "F11") (pinfunction "GND_40_F11") (pintype "bidirectional"))
      (node (ref "U3") (pin "F16") (pinfunction "GND_41_F16") (pintype "bidirectional"))
      (node (ref "U3") (pin "F21") (pinfunction "GND_42_F21") (pintype "bidirectional"))
      (node (ref "U3") (pin "F26") (pinfunction "GND_43_F26") (pintype "bidirectional"))
      (node (ref "U3") (pin "F3") (pinfunction "GND_37_F3") (pintype "bidirectional"))
      (node (ref "U3") (pin "F4") (pinfunction "GND_38_F4") (pintype "bidirectional"))
      (node (ref "U3") (pin "F8") (pinfunction "GND_39_F8") (pintype "bidirectional"))
      (node (ref "U3") (pin "G1") (pinfunction "GND_44_G1") (pintype "bidirectional"))
      (node (ref "U3") (pin "G13") (pinfunction "GND_49_G13") (pintype "bidirectional"))
      (node (ref "U3") (pin "G2") (pinfunction "GND_45_G2") (pintype "bidirectional"))
      (node (ref "U3") (pin "G23") (pinfunction "GND_50_G23") (pintype "bidirectional"))
      (node (ref "U3") (pin "G3") (pinfunction "GND_46_G3") (pintype "bidirectional"))
      (node (ref "U3") (pin "G6") (pinfunction "GND_47_G6") (pintype "bidirectional"))
      (node (ref "U3") (pin "G8") (pinfunction "GND_48_G8") (pintype "bidirectional"))
      (node (ref "U3") (pin "H20") (pinfunction "GND_54_H20") (pintype "bidirectional"))
      (node (ref "U3") (pin "H3") (pinfunction "GND_51_H3") (pintype "bidirectional"))
      (node (ref "U3") (pin "H4") (pinfunction "GND_52_H4") (pintype "bidirectional"))
      (node (ref "U3") (pin "H8") (pinfunction "GND_53_H8") (pintype "bidirectional"))
      (node (ref "U3") (pin "J1") (pinfunction "GND_55_J1") (pintype "bidirectional"))
      (node (ref "U3") (pin "J17") (pinfunction "GND_60_J17") (pintype "bidirectional"))
      (node (ref "U3") (pin "J2") (pinfunction "GND_56_J2") (pintype "bidirectional"))
      (node (ref "U3") (pin "J3") (pinfunction "GND_57_J3") (pintype "bidirectional"))
      (node (ref "U3") (pin "J6") (pinfunction "GND_58_J6") (pintype "bidirectional"))
      (node (ref "U3") (pin "J8") (pinfunction "GND_59_J8") (pintype "bidirectional"))
      (node (ref "U3") (pin "K12") (pinfunction "GND_64_K12") (pintype "bidirectional"))
      (node (ref "U3") (pin "K14") (pinfunction "GND_65_K14") (pintype "bidirectional"))
      (node (ref "U3") (pin "K16") (pinfunction "GND_66_K16") (pintype "bidirectional"))
      (node (ref "U3") (pin "K19") (pinfunction "GND_67_K19") (pintype "bidirectional"))
      (node (ref "U3") (pin "K24") (pinfunction "GND_68_K24") (pintype "bidirectional"))
      (node (ref "U3") (pin "K3") (pinfunction "GND_61_K3") (pintype "bidirectional"))
      (node (ref "U3") (pin "K4") (pinfunction "GND_62_K4") (pintype "bidirectional"))
      (node (ref "U3") (pin "K8") (pinfunction "GND_63_K8") (pintype "bidirectional"))
      (node (ref "U3") (pin "L1") (pinfunction "GND_69_L1") (pintype "bidirectional"))
      (node (ref "U3") (pin "L11") (pinfunction "GND_74_L11") (pintype "bidirectional"))
      (node (ref "U3") (pin "L13") (pinfunction "GND_75_L13") (pintype "bidirectional"))
      (node (ref "U3") (pin "L15") (pinfunction "GND_76_L15") (pintype "bidirectional"))
      (node (ref "U3") (pin "L17") (pinfunction "GND_77_L17") (pintype "bidirectional"))
      (node (ref "U3") (pin "L2") (pinfunction "GND_70_L2") (pintype "bidirectional"))
      (node (ref "U3") (pin "L21") (pinfunction "GND_78_L21") (pintype "bidirectional"))
      (node (ref "U3") (pin "L26") (pinfunction "GND_79_L26") (pintype "bidirectional"))
      (node (ref "U3") (pin "L3") (pinfunction "GND_71_L3") (pintype "bidirectional"))
      (node (ref "U3") (pin "L6") (pinfunction "GND_72_L6") (pintype "bidirectional"))
      (node (ref "U3") (pin "L8") (pinfunction "GND_73_L8") (pintype "bidirectional"))
      (node (ref "U3") (pin "M10") (pinfunction "GND_83_M10") (pintype "bidirectional"))
      (node (ref "U3") (pin "M12") (pinfunction "GND_84_M12") (pintype "bidirectional"))
      (node (ref "U3") (pin "M14") (pinfunction "GND_85_M14") (pintype "bidirectional"))
      (node (ref "U3") (pin "M16") (pinfunction "GND_86_M16") (pintype "bidirectional"))
      (node (ref "U3") (pin "M23") (pinfunction "GND_87_M23") (pintype "bidirectional"))
      (node (ref "U3") (pin "M3") (pinfunction "GND_80_M3") (pintype "bidirectional"))
      (node (ref "U3") (pin "M4") (pinfunction "GND_81_M4") (pintype "bidirectional"))
      (node (ref "U3") (pin "M8") (pinfunction "GND_82_M8") (pintype "bidirectional"))
      (node (ref "U3") (pin "N1") (pinfunction "GND_88_N1") (pintype "bidirectional"))
      (node (ref "U3") (pin "N11") (pinfunction "GND_93_N11") (pintype "bidirectional"))
      (node (ref "U3") (pin "N15") (pinfunction "GND_94_N15") (pintype "bidirectional"))
      (node (ref "U3") (pin "N17") (pinfunction "GND_95_N17") (pintype "bidirectional"))
      (node (ref "U3") (pin "N2") (pinfunction "GND_89_N2") (pintype "bidirectional"))
      (node (ref "U3") (pin "N20") (pinfunction "GND_96_N20") (pintype "bidirectional"))
      (node (ref "U3") (pin "N25") (pinfunction "GND_97_N25") (pintype "bidirectional"))
      (node (ref "U3") (pin "N3") (pinfunction "GND_90_N3") (pintype "bidirectional"))
      (node (ref "U3") (pin "N6") (pinfunction "GND_91_N6") (pintype "bidirectional"))
      (node (ref "U3") (pin "N8") (pinfunction "GND_92_N8") (pintype "bidirectional"))
      (node (ref "U3") (pin "P10") (pinfunction "GND_101_P10") (pintype "bidirectional"))
      (node (ref "U3") (pin "P12") (pinfunction "GND_102_P12") (pintype "bidirectional"))
      (node (ref "U3") (pin "P16") (pinfunction "GND_103_P16") (pintype "bidirectional"))
      (node (ref "U3") (pin "P3") (pinfunction "GND_98_P3") (pintype "bidirectional"))
      (node (ref "U3") (pin "P4") (pinfunction "GND_99_P4") (pintype "bidirectional"))
      (node (ref "U3") (pin "P8") (pinfunction "GND_100_P8") (pintype "bidirectional"))
      (node (ref "U3") (pin "R1") (pinfunction "GND_104_R1") (pintype "bidirectional"))
      (node (ref "U3") (pin "R11") (pinfunction "GND_109_R11") (pintype "bidirectional"))
      (node (ref "U3") (pin "R15") (pinfunction "GND_110_R15") (pintype "bidirectional"))
      (node (ref "U3") (pin "R17") (pinfunction "GND_111_R17") (pintype "bidirectional"))
      (node (ref "U3") (pin "R19") (pinfunction "GND_112_R19") (pintype "bidirectional"))
      (node (ref "U3") (pin "R2") (pinfunction "GND_105_R2") (pintype "bidirectional"))
      (node (ref "U3") (pin "R24") (pinfunction "GND_113_R24") (pintype "bidirectional"))
      (node (ref "U3") (pin "R3") (pinfunction "GND_106_R3") (pintype "bidirectional"))
      (node (ref "U3") (pin "R6") (pinfunction "GND_107_R6") (pintype "bidirectional"))
      (node (ref "U3") (pin "R8") (pinfunction "GND_108_R8") (pintype "bidirectional"))
      (node (ref "U3") (pin "T10") (pinfunction "GND_117_T10") (pintype "bidirectional"))
      (node (ref "U3") (pin "T12") (pinfunction "GND_118_T12") (pintype "bidirectional"))
      (node (ref "U3") (pin "T13") (pinfunction "DXN_T13") (pintype "bidirectional"))
      (node (ref "U3") (pin "T14") (pinfunction "DXP_T14") (pintype "bidirectional"))
      (node (ref "U3") (pin "T16") (pinfunction "GND_119_T16") (pintype "bidirectional"))
      (node (ref "U3") (pin "T21") (pinfunction "GND_120_T21") (pintype "bidirectional"))
      (node (ref "U3") (pin "T26") (pinfunction "GND_121_T26") (pintype "bidirectional"))
      (node (ref "U3") (pin "T3") (pinfunction "GND_114_T3") (pintype "bidirectional"))
      (node (ref "U3") (pin "T4") (pinfunction "GND_115_T4") (pintype "bidirectional"))
      (node (ref "U3") (pin "T8") (pinfunction "GND_116_T8") (pintype "bidirectional"))
      (node (ref "U3") (pin "U1") (pinfunction "GND_122_U1") (pintype "bidirectional"))
      (node (ref "U3") (pin "U11") (pinfunction "GND_127_U11") (pintype "bidirectional"))
      (node (ref "U3") (pin "U13") (pinfunction "GND_128_U13") (pintype "bidirectional"))
      (node (ref "U3") (pin "U15") (pinfunction "GND_129_U15") (pintype "bidirectional"))
      (node (ref "U3") (pin "U17") (pinfunction "GND_130_U17") (pintype "bidirectional"))
      (node (ref "U3") (pin "U18") (pinfunction "GND_131_U18") (pintype "bidirectional"))
      (node (ref "U3") (pin "U2") (pinfunction "GND_123_U2") (pintype "bidirectional"))
      (node (ref "U3") (pin "U3") (pinfunction "GND_124_U3") (pintype "bidirectional"))
      (node (ref "U3") (pin "U6") (pinfunction "GND_125_U6") (pintype "bidirectional"))
      (node (ref "U3") (pin "U8") (pinfunction "GND_126_U8") (pintype "bidirectional"))
      (node (ref "U3") (pin "V10") (pinfunction "GND_135_V10") (pintype "bidirectional"))
      (node (ref "U3") (pin "V12") (pinfunction "GND_136_V12") (pintype "bidirectional"))
      (node (ref "U3") (pin "V14") (pinfunction "GND_137_V14") (pintype "bidirectional"))
      (node (ref "U3") (pin "V16") (pinfunction "GND_138_V16") (pintype "bidirectional"))
      (node (ref "U3") (pin "V20") (pinfunction "GND_139_V20") (pintype "bidirectional"))
      (node (ref "U3") (pin "V25") (pinfunction "GND_140_V25") (pintype "bidirectional"))
      (node (ref "U3") (pin "V3") (pinfunction "GND_132_V3") (pintype "bidirectional"))
      (node (ref "U3") (pin "V4") (pinfunction "GND_133_V4") (pintype "bidirectional"))
      (node (ref "U3") (pin "V8") (pinfunction "GND_134_V8") (pintype "bidirectional"))
      (node (ref "U3") (pin "W1") (pinfunction "GND_141_W1") (pintype "bidirectional"))
      (node (ref "U3") (pin "W11") (pinfunction "RSVDGND_W11") (pintype "bidirectional"))
      (node (ref "U3") (pin "W17") (pinfunction "GND_146_W17") (pintype "bidirectional"))
      (node (ref "U3") (pin "W2") (pinfunction "GND_142_W2") (pintype "bidirectional"))
      (node (ref "U3") (pin "W22") (pinfunction "GND_147_W22") (pintype "bidirectional"))
      (node (ref "U3") (pin "W3") (pinfunction "GND_143_W3") (pintype "bidirectional"))
      (node (ref "U3") (pin "W6") (pinfunction "GND_144_W6") (pintype "bidirectional"))
      (node (ref "U3") (pin "W8") (pinfunction "GND_145_W8") (pintype "bidirectional"))
      (node (ref "U3") (pin "Y19") (pinfunction "GND_151_Y19") (pintype "bidirectional"))
      (node (ref "U3") (pin "Y3") (pinfunction "GND_148_Y3") (pintype "bidirectional"))
      (node (ref "U3") (pin "Y4") (pinfunction "GND_149_Y4") (pintype "bidirectional"))
      (node (ref "U3") (pin "Y8") (pinfunction "GND_150_Y8") (pintype "bidirectional"))
    )
    (net (code "17") (name "GNDADC") (class "Default")
      (node (ref "C167") (pin "1") (pinfunction "1_1") (pintype "passive"))
      (node (ref "C168") (pin "1") (pinfunction "1_1") (pintype "passive"))
      (node (ref "FB4") (pin "1") (pinfunction "1_1") (pintype "passive"))
      (node (ref "U3") (pin "N13") (pinfunction "GNDADC_N13") (pintype "bidirectional"))
      (node (ref "U3") (pin "P13") (pinfunction "VREFN_P13") (pintype "bidirectional"))
      (node (ref "U3") (pin "P14") (pinfunction "VP_P14") (pintype "bidirectional"))
      (node (ref "U3") (pin "R13") (pinfunction "VN_R13") (pintype "bidirectional"))
      (node (ref "U3") (pin "R14") (pinfunction "VREFP_R14") (pintype "bidirectional"))
    )
    (net (code "18") (name "Net-(U3A-DONE_0)") (class "Default")
      (node (ref "R99") (pin "2") (pinfunction "2_2") (pintype "passive"))
      (node (ref "U3") (pin "AB11") (pinfunction "DONE_0_AB11") (pintype "bidirectional"))
    )
    (net (code "19") (name "Net-(U3A-INIT_B_0)") (class "Default")
      (node (ref "R98") (pin "2") (pinfunction "2_2") (pintype "passive"))
      (node (ref "U3") (pin "W10") (pinfunction "INIT_B_0_W10") (pintype "bidirectional"))
    )
    (net (code "20") (name "Net-(U3A-M0_0)") (class "Default")
      (node (ref "R93") (pin "1") (pinfunction "1_1") (pintype "passive"))
      (node (ref "U3") (pin "AA10") (pinfunction "M0_0_AA10") (pintype "bidirectional"))
    )
    (net (code "21") (name "Net-(U3A-M1_0)") (class "Default")
      (node (ref "R96") (pin "1") (pinfunction "1_1") (pintype "passive"))
      (node (ref "U3") (pin "AA9") (pinfunction "M1_0_AA9") (pintype "bidirectional"))
    )
    (net (code "22") (name "Net-(U3A-M2_0)") (class "Default")
      (node (ref "R97") (pin "1") (pinfunction "1_1") (pintype "passive"))
      (node (ref "U3") (pin "AF12") (pinfunction "M2_0_AF12") (pintype "bidirectional"))
    )
    (net (code "23") (name "Net-(U3A-PUDC_B_0)") (class "Default")
      (node (ref "R102") (pin "1") (pinfunction "1_1") (pintype "passive"))
      (node (ref "U3") (pin "W9") (pinfunction "PUDC_B_0_W9") (pintype "bidirectional"))
    )
    (net (code "24") (name "Net-(U3M-MGTRREF_R)") (class "Default")
      (node (ref "R107") (pin "1") (pinfunction "1_1") (pintype "passive"))
      (node (ref "U3") (pin "AD9") (pinfunction "MGTRREF_R_AD9") (pintype "bidirectional"))
    )
    (net (code "25") (name "Net-(U3O-POR_OVERRIDE)") (class "Default")
      (node (ref "R106") (pin "2") (pinfunction "2_2") (pintype "passive"))
      (node (ref "U3") (pin "Y12") (pinfunction "POR_OVERRIDE_Y12") (pintype "bidirectional"))
    )
    (net (code "26") (name "Net-(U14-SI(IO0))") (class "Default")
      (node (ref "R92") (pin "2") (pinfunction "2_2") (pintype "passive"))
      (node (ref "U14") (pin "5") (pinfunction "SI(IO0)_5") (pintype "bidirectional"))
    )
    (net (code "27") (name "Net-(U14-SO(IO1))") (class "Default")
      (node (ref "R95") (pin "2") (pinfunction "2_2") (pintype "passive"))
      (node (ref "U14") (pin "2") (pinfunction "SO(IO1)_2") (pintype "bidirectional"))
    )
    (net (code "28") (name "Net-(U14-~{HOLD}{slash}RESET(IO3))") (class "Default")
      (node (ref "R94") (pin "1") (pinfunction "1_1") (pintype "passive"))
      (node (ref "U14") (pin "7") (pinfunction "~{HOLD}/RESET(IO3)_7") (pintype "bidirectional"))
    )
    (net (code "29") (name "Net-(U14-~{WP(IO2)})") (class "Default")
      (node (ref "R89") (pin "2") (pinfunction "2_2") (pintype "passive"))
      (node (ref "U14") (pin "3") (pinfunction "~{WP(IO2)}_3") (pintype "bidirectional"))
    )
    (net (code "30") (name "VBATT") (class "Default")
      (node (ref "R105") (pin "2") (pinfunction "2_2") (pintype "passive"))
      (node (ref "T9") (pin "1") (pintype "passive"))
      (node (ref "U3") (pin "Y9") (pinfunction "VBATT_Y9") (pintype "bidirectional"))
    )
    (net (code "31") (name "VCCADC") (class "Default")
      (node (ref "C167") (pin "2") (pinfunction "2_2") (pintype "passive"))
      (node (ref "C168") (pin "2") (pinfunction "2_2") (pintype "passive"))
      (node (ref "FB3") (pin "1") (pinfunction "1_1") (pintype "passive"))
      (node (ref "U3") (pin "N14") (pinfunction "VCCADC_N14") (pintype "bidirectional"))
    )
    (net (code "32") (name "VCCINT") (class "Default")
      (node (ref "C156") (pin "1") (pinfunction "1_1") (pintype "passive"))
      (node (ref "C157") (pin "1") (pinfunction "1_1") (pintype "passive"))
      (node (ref "C158") (pin "1") (pinfunction "1_1") (pintype "passive"))
      (node (ref "C159") (pin "1") (pinfunction "1_1") (pintype "passive"))
      (node (ref "C160") (pin "1") (pinfunction "1_1") (pintype "passive"))
      (node (ref "C161") (pin "1") (pinfunction "1_1") (pintype "passive"))
      (node (ref "C162") (pin "2") (pinfunction "2_2") (pintype "passive"))
      (node (ref "C165") (pin "2") (pinfunction "2_2") (pintype "passive"))
      (node (ref "C166") (pin "1") (pinfunction "1_1") (pintype "passive"))
      (node (ref "U3") (pin "K11") (pinfunction "VCCINT_1_K11") (pintype "bidirectional"))
      (node (ref "U3") (pin "K13") (pinfunction "VCCINT_2_K13") (pintype "bidirectional"))
      (node (ref "U3") (pin "K15") (pinfunction "VCCINT_3_K15") (pintype "bidirectional"))
      (node (ref "U3") (pin "K17") (pinfunction "VCCINT_4_K17") (pintype "bidirectional"))
      (node (ref "U3") (pin "L10") (pinfunction "VCCINT_5_L10") (pintype "bidirectional"))
      (node (ref "U3") (pin "L12") (pinfunction "VCCINT_6_L12") (pintype "bidirectional"))
      (node (ref "U3") (pin "L14") (pinfunction "VCCINT_7_L14") (pintype "bidirectional"))
      (node (ref "U3") (pin "L16") (pinfunction "VCCINT_8_L16") (pintype "bidirectional"))
      (node (ref "U3") (pin "L9") (pinfunction "VCCINT_IO_1_L9") (pintype "bidirectional"))
      (node (ref "U3") (pin "M11") (pinfunction "VCCINT_9_M11") (pintype "bidirectional"))
      (node (ref "U3") (pin "M13") (pinfunction "VCCINT_10_M13") (pintype "bidirectional"))
      (node (ref "U3") (pin "M15") (pinfunction "VCCINT_11_M15") (pintype "bidirectional"))
      (node (ref "U3") (pin "M17") (pinfunction "VCCINT_12_M17") (pintype "bidirectional"))
      (node (ref "U3") (pin "M9") (pinfunction "VCCINT_IO_2_M9") (pintype "bidirectional"))
      (node (ref "U3") (pin "N10") (pinfunction "VCCINT_13_N10") (pintype "bidirectional"))
      (node (ref "U3") (pin "N12") (pinfunction "VCCINT_14_N12") (pintype "bidirectional"))
      (node (ref "U3") (pin "N16") (pinfunction "VCCINT_15_N16") (pintype "bidirectional"))
      (node (ref "U3") (pin "N9") (pinfunction "VCCINT_IO_3_N9") (pintype "bidirectional"))
      (node (ref "U3") (pin "P11") (pinfunction "VCCINT_16_P11") (pintype "bidirectional"))
      (node (ref "U3") (pin "P15") (pinfunction "VCCINT_17_P15") (pintype "bidirectional"))
      (node (ref "U3") (pin "P17") (pinfunction "VCCINT_18_P17") (pintype "bidirectional"))
      (node (ref "U3") (pin "P9") (pinfunction "VCCINT_IO_4_P9") (pintype "bidirectional"))
      (node (ref "U3") (pin "R10") (pinfunction "VCCINT_19_R10") (pintype "bidirectional"))
      (node (ref "U3") (pin "R12") (pinfunction "VCCINT_20_R12") (pintype "bidirectional"))
      (node (ref "U3") (pin "R16") (pinfunction "VCCINT_21_R16") (pintype "bidirectional"))
      (node (ref "U3") (pin "R9") (pinfunction "VCCBRAM_1_R9") (pintype "bidirectional"))
      (node (ref "U3") (pin "T11") (pinfunction "VCCINT_22_T11") (pintype "bidirectional"))
      (node (ref "U3") (pin "T15") (pinfunction "VCCINT_23_T15") (pintype "bidirectional"))
      (node (ref "U3") (pin "T17") (pinfunction "VCCINT_24_T17") (pintype "bidirectional"))
      (node (ref "U3") (pin "T9") (pinfunction "VCCBRAM_2_T9") (pintype "bidirectional"))
      (node (ref "U3") (pin "U10") (pinfunction "VCCINT_25_U10") (pintype "bidirectional"))
      (node (ref "U3") (pin "U12") (pinfunction "VCCINT_26_U12") (pintype "bidirectional"))
      (node (ref "U3") (pin "U14") (pinfunction "VCCINT_27_U14") (pintype "bidirectional"))
      (node (ref "U3") (pin "U16") (pinfunction "VCCINT_28_U16") (pintype "bidirectional"))
      (node (ref "U3") (pin "U9") (pinfunction "VCCBRAM_3_U9") (pintype "bidirectional"))
      (node (ref "U3") (pin "V11") (pinfunction "VCCINT_29_V11") (pintype "bidirectional"))
      (node (ref "U3") (pin "V13") (pinfunction "VCCINT_30_V13") (pintype "bidirectional"))
      (node (ref "U3") (pin "V15") (pinfunction "VCCINT_31_V15") (pintype "bidirectional"))
      (node (ref "U3") (pin "V17") (pinfunction "VCCINT_32_V17") (pintype "bidirectional"))
      (node (ref "U3") (pin "V9") (pinfunction "VCCBRAM_4_V9") (pintype "bidirectional"))
    )
    (net (code "33") (name "unconnected-(J7-Pad12)") (class "Default")
      (node (ref "J7") (pin "12") (pinfunction "12_12") (pintype "passive+no_connect"))
    )
    (net (code "34") (name "unconnected-(J7-Pad14)") (class "Default")
      (node (ref "J7") (pin "14") (pinfunction "14_14") (pintype "passive+no_connect"))
    )
    (net (code "35") (name "unconnected-(U3P-NC_1-PadA3)") (class "Default")
      (node (ref "U3") (pin "A3") (pinfunction "NC_1_A3") (pintype "bidirectional"))
    )
    (net (code "36") (name "unconnected-(U3P-NC_2-PadA4)") (class "Default")
      (node (ref "U3") (pin "A4") (pinfunction "NC_2_A4") (pintype "bidirectional"))
    )
    (net (code "37") (name "unconnected-(U3P-NC_3-PadA15)") (class "Default")
      (node (ref "U3") (pin "A15") (pinfunction "NC_3_A15") (pintype "bidirectional"))
    )
    (net (code "38") (name "unconnected-(U3P-NC_4-PadA17)") (class "Default")
      (node (ref "U3") (pin "A17") (pinfunction "NC_4_A17") (pintype "bidirectional"))
    )
    (net (code "39") (name "unconnected-(U3P-NC_5-PadA18)") (class "Default")
      (node (ref "U3") (pin "A18") (pinfunction "NC_5_A18") (pintype "bidirectional"))
    )
    (net (code "40") (name "unconnected-(U3P-NC_6-PadA19)") (class "Default")
      (node (ref "U3") (pin "A19") (pinfunction "NC_6_A19") (pintype "bidirectional"))
    )
    (net (code "41") (name "unconnected-(U3P-NC_7-PadA20)") (class "Default")
      (node (ref "U3") (pin "A20") (pinfunction "NC_7_A20") (pintype "bidirectional"))
    )
    (net (code "42") (name "unconnected-(U3P-NC_8-PadA22)") (class "Default")
      (node (ref "U3") (pin "A22") (pinfunction "NC_8_A22") (pintype "bidirectional"))
    )
    (net (code "43") (name "unconnected-(U3P-NC_9-PadA23)") (class "Default")
      (node (ref "U3") (pin "A23") (pinfunction "NC_9_A23") (pintype "bidirectional"))
    )
    (net (code "44") (name "unconnected-(U3P-NC_10-PadA24)") (class "Default")
      (node (ref "U3") (pin "A24") (pinfunction "NC_10_A24") (pintype "bidirectional"))
    )
    (net (code "45") (name "unconnected-(U3P-NC_11-PadA25)") (class "Default")
      (node (ref "U3") (pin "A25") (pinfunction "NC_11_A25") (pintype "bidirectional"))
    )
    (net (code "46") (name "unconnected-(U3P-NC_12-PadB1)") (class "Default")
      (node (ref "U3") (pin "B1") (pinfunction "NC_12_B1") (pintype "bidirectional"))
    )
    (net (code "47") (name "unconnected-(U3P-NC_13-PadB2)") (class "Default")
      (node (ref "U3") (pin "B2") (pinfunction "NC_13_B2") (pintype "bidirectional"))
    )
    (net (code "48") (name "unconnected-(U3P-NC_14-PadB6)") (class "Default")
      (node (ref "U3") (pin "B6") (pinfunction "NC_14_B6") (pintype "bidirectional"))
    )
    (net (code "49") (name "unconnected-(U3P-NC_15-PadB7)") (class "Default")
      (node (ref "U3") (pin "B7") (pinfunction "NC_15_B7") (pintype "bidirectional"))
    )
    (net (code "50") (name "unconnected-(U3P-NC_16-PadB15)") (class "Default")
      (node (ref "U3") (pin "B15") (pinfunction "NC_16_B15") (pintype "bidirectional"))
    )
    (net (code "51") (name "unconnected-(U3P-NC_17-PadB16)") (class "Default")
      (node (ref "U3") (pin "B16") (pinfunction "NC_17_B16") (pintype "bidirectional"))
    )
    (net (code "52") (name "unconnected-(U3P-NC_18-PadB17)") (class "Default")
      (node (ref "U3") (pin "B17") (pinfunction "NC_18_B17") (pintype "bidirectional"))
    )
    (net (code "53") (name "unconnected-(U3P-NC_19-PadB19)") (class "Default")
      (node (ref "U3") (pin "B19") (pinfunction "NC_19_B19") (pintype "bidirectional"))
    )
    (net (code "54") (name "unconnected-(U3P-NC_20-PadB20)") (class "Default")
      (node (ref "U3") (pin "B20") (pinfunction "NC_20_B20") (pintype "bidirectional"))
    )
    (net (code "55") (name "unconnected-(U3P-NC_21-PadB21)") (class "Default")
      (node (ref "U3") (pin "B21") (pinfunction "NC_21_B21") (pintype "bidirectional"))
    )
    (net (code "56") (name "unconnected-(U3P-NC_22-PadB22)") (class "Default")
      (node (ref "U3") (pin "B22") (pinfunction "NC_22_B22") (pintype "bidirectional"))
    )
    (net (code "57") (name "unconnected-(U3P-NC_23-PadB24)") (class "Default")
      (node (ref "U3") (pin "B24") (pinfunction "NC_23_B24") (pintype "bidirectional"))
    )
    (net (code "58") (name "unconnected-(U3P-NC_24-PadC3)") (class "Default")
      (node (ref "U3") (pin "C3") (pinfunction "NC_24_C3") (pintype "bidirectional"))
    )
    (net (code "59") (name "unconnected-(U3P-NC_25-PadC4)") (class "Default")
      (node (ref "U3") (pin "C4") (pinfunction "NC_25_C4") (pintype "bidirectional"))
    )
    (net (code "60") (name "unconnected-(U3P-NC_26-PadC16)") (class "Default")
      (node (ref "U3") (pin "C16") (pinfunction "NC_26_C16") (pintype "bidirectional"))
    )
    (net (code "61") (name "unconnected-(U3P-NC_27-PadC17)") (class "Default")
      (node (ref "U3") (pin "C17") (pinfunction "NC_27_C17") (pintype "bidirectional"))
    )
    (net (code "62") (name "unconnected-(U3P-NC_28-PadC18)") (class "Default")
      (node (ref "U3") (pin "C18") (pinfunction "NC_28_C18") (pintype "bidirectional"))
    )
    (net (code "63") (name "unconnected-(U3P-NC_29-PadC19)") (class "Default")
      (node (ref "U3") (pin "C19") (pinfunction "NC_29_C19") (pintype "bidirectional"))
    )
    (net (code "64") (name "unconnected-(U3P-NC_30-PadC20)") (class "Default")
      (node (ref "U3") (pin "C20") (pinfunction "NC_30_C20") (pintype "bidirectional"))
    )
    (net (code "65") (name "unconnected-(U3P-NC_31-PadC21)") (class "Default")
      (node (ref "U3") (pin "C21") (pinfunction "NC_31_C21") (pintype "bidirectional"))
    )
    (net (code "66") (name "unconnected-(U3P-NC_32-PadC22)") (class "Default")
      (node (ref "U3") (pin "C22") (pinfunction "NC_32_C22") (pintype "bidirectional"))
    )
    (net (code "67") (name "unconnected-(U3P-NC_33-PadC23)") (class "Default")
      (node (ref "U3") (pin "C23") (pinfunction "NC_33_C23") (pintype "bidirectional"))
    )
    (net (code "68") (name "unconnected-(U3P-NC_34-PadD1)") (class "Default")
      (node (ref "U3") (pin "D1") (pinfunction "NC_34_D1") (pintype "bidirectional"))
    )
    (net (code "69") (name "unconnected-(U3P-NC_35-PadD2)") (class "Default")
      (node (ref "U3") (pin "D2") (pinfunction "NC_35_D2") (pintype "bidirectional"))
    )
    (net (code "70") (name "unconnected-(U3P-NC_36-PadD6)") (class "Default")
      (node (ref "U3") (pin "D6") (pinfunction "NC_36_D6") (pintype "bidirectional"))
    )
    (net (code "71") (name "unconnected-(U3P-NC_37-PadD7)") (class "Default")
      (node (ref "U3") (pin "D7") (pinfunction "NC_37_D7") (pintype "bidirectional"))
    )
    (net (code "72") (name "unconnected-(U3P-NC_38-PadD15)") (class "Default")
      (node (ref "U3") (pin "D15") (pinfunction "NC_38_D15") (pintype "bidirectional"))
    )
    (net (code "73") (name "unconnected-(U3P-NC_39-PadD16)") (class "Default")
      (node (ref "U3") (pin "D16") (pinfunction "NC_39_D16") (pintype "bidirectional"))
    )
    (net (code "74") (name "unconnected-(U3P-NC_40-PadD17)") (class "Default")
      (node (ref "U3") (pin "D17") (pinfunction "NC_40_D17") (pintype "bidirectional"))
    )
    (net (code "75") (name "unconnected-(U3P-NC_41-PadD18)") (class "Default")
      (node (ref "U3") (pin "D18") (pinfunction "NC_41_D18") (pintype "bidirectional"))
    )
    (net (code "76") (name "unconnected-(U3P-NC_42-PadD19)") (class "Default")
      (node (ref "U3") (pin "D19") (pinfunction "NC_42_D19") (pintype "bidirectional"))
    )
    (net (code "77") (name "unconnected-(U3P-NC_43-PadD20)") (class "Default")
      (node (ref "U3") (pin "D20") (pinfunction "NC_43_D20") (pintype "bidirectional"))
    )
    (net (code "78") (name "unconnected-(U3P-NC_44-PadD21)") (class "Default")
      (node (ref "U3") (pin "D21") (pinfunction "NC_44_D21") (pintype "bidirectional"))
    )
    (net (code "79") (name "unconnected-(U3P-NC_45-PadE4)") (class "Default")
      (node (ref "U3") (pin "E4") (pinfunction "NC_45_E4") (pintype "bidirectional"))
    )
    (net (code "80") (name "unconnected-(U3P-NC_46-PadE5)") (class "Default")
      (node (ref "U3") (pin "E5") (pinfunction "NC_46_E5") (pintype "bidirectional"))
    )
    (net (code "81") (name "unconnected-(U3P-NC_47-PadE15)") (class "Default")
      (node (ref "U3") (pin "E15") (pinfunction "NC_47_E15") (pintype "bidirectional"))
    )
    (net (code "82") (name "unconnected-(U3P-NC_48-PadE16)") (class "Default")
      (node (ref "U3") (pin "E16") (pinfunction "NC_48_E16") (pintype "bidirectional"))
    )
    (net (code "83") (name "unconnected-(U3P-NC_49-PadE17)") (class "Default")
      (node (ref "U3") (pin "E17") (pinfunction "NC_49_E17") (pintype "bidirectional"))
    )
    (net (code "84") (name "unconnected-(U3P-NC_50-PadE18)") (class "Default")
      (node (ref "U3") (pin "E18") (pinfunction "NC_50_E18") (pintype "bidirectional"))
    )
    (net (code "85") (name "unconnected-(U3P-NC_51-PadE20)") (class "Default")
      (node (ref "U3") (pin "E20") (pinfunction "NC_51_E20") (pintype "bidirectional"))
    )
    (net (code "86") (name "unconnected-(U3P-NC_52-PadE21)") (class "Default")
      (node (ref "U3") (pin "E21") (pinfunction "NC_52_E21") (pintype "bidirectional"))
    )
    (net (code "87") (name "unconnected-(U3P-NC_53-PadE22)") (class "Default")
      (node (ref "U3") (pin "E22") (pinfunction "NC_53_E22") (pintype "bidirectional"))
    )
    (net (code "88") (name "unconnected-(U3P-NC_54-PadF6)") (class "Default")
      (node (ref "U3") (pin "F6") (pinfunction "NC_54_F6") (pintype "bidirectional"))
    )
    (net (code "89") (name "unconnected-(U3P-NC_55-PadF7)") (class "Default")
      (node (ref "U3") (pin "F7") (pinfunction "NC_55_F7") (pintype "bidirectional"))
    )
    (net (code "90") (name "unconnected-(U3P-NC_56-PadF15)") (class "Default")
      (node (ref "U3") (pin "F15") (pinfunction "NC_56_F15") (pintype "bidirectional"))
    )
    (net (code "91") (name "unconnected-(U3P-NC_57-PadF17)") (class "Default")
      (node (ref "U3") (pin "F17") (pinfunction "NC_57_F17") (pintype "bidirectional"))
    )
    (net (code "92") (name "unconnected-(U3P-NC_58-PadF18)") (class "Default")
      (node (ref "U3") (pin "F18") (pinfunction "NC_58_F18") (pintype "bidirectional"))
    )
    (net (code "93") (name "unconnected-(U3P-NC_59-PadF19)") (class "Default")
      (node (ref "U3") (pin "F19") (pinfunction "NC_59_F19") (pintype "bidirectional"))
    )
    (net (code "94") (name "unconnected-(U3P-NC_60-PadF20)") (class "Default")
      (node (ref "U3") (pin "F20") (pinfunction "NC_60_F20") (pintype "bidirectional"))
    )
    (net (code "95") (name "unconnected-(U3P-NC_61-PadG15)") (class "Default")
      (node (ref "U3") (pin "G15") (pinfunction "NC_61_G15") (pintype "bidirectional"))
    )
    (net (code "96") (name "unconnected-(U3P-NC_62-PadG16)") (class "Default")
      (node (ref "U3") (pin "G16") (pinfunction "NC_62_G16") (pintype "bidirectional"))
    )
    (net (code "97") (name "unconnected-(U3P-NC_63-PadG17)") (class "Default")
      (node (ref "U3") (pin "G17") (pinfunction "NC_63_G17") (pintype "bidirectional"))
    )
    (net (code "98") (name "unconnected-(U3P-NC_64-PadG18)") (class "Default")
      (node (ref "U3") (pin "G18") (pinfunction "NC_64_G18") (pintype "bidirectional"))
    )
    (net (code "99") (name "unconnected-(U3P-NC_65-PadG19)") (class "Default")
      (node (ref "U3") (pin "G19") (pinfunction "NC_65_G19") (pintype "bidirectional"))
    )
    (net (code "100") (name "unconnected-(U3P-NC_66-PadG20)") (class "Default")
      (node (ref "U3") (pin "G20") (pinfunction "NC_66_G20") (pintype "bidirectional"))
    )
    (net (code "101") (name "unconnected-(U3P-NC_67-PadG21)") (class "Default")
      (node (ref "U3") (pin "G21") (pinfunction "NC_67_G21") (pintype "bidirectional"))
    )
    (net (code "102") (name "unconnected-(U3P-NC_68-PadH6)") (class "Default")
      (node (ref "U3") (pin "H6") (pinfunction "NC_68_H6") (pintype "bidirectional"))
    )
    (net (code "103") (name "unconnected-(U3P-NC_69-PadH7)") (class "Default")
      (node (ref "U3") (pin "H7") (pinfunction "NC_69_H7") (pintype "bidirectional"))
    )
    (net (code "104") (name "unconnected-(U3P-NC_70-PadH16)") (class "Default")
      (node (ref "U3") (pin "H16") (pinfunction "NC_70_H16") (pintype "bidirectional"))
    )
    (net (code "105") (name "unconnected-(U3P-NC_71-PadH17)") (class "Default")
      (node (ref "U3") (pin "H17") (pinfunction "NC_71_H17") (pintype "bidirectional"))
    )
    (net (code "106") (name "unconnected-(U3P-NC_72-PadH18)") (class "Default")
      (node (ref "U3") (pin "H18") (pinfunction "NC_72_H18") (pintype "bidirectional"))
    )
    (net (code "107") (name "unconnected-(U3P-NC_73-PadH19)") (class "Default")
      (node (ref "U3") (pin "H19") (pinfunction "NC_73_H19") (pintype "bidirectional"))
    )
    (net (code "108") (name "unconnected-(U3P-NC_74-PadJ16)") (class "Default")
      (node (ref "U3") (pin "J16") (pinfunction "NC_74_J16") (pintype "bidirectional"))
    )
    (net (code "109") (name "unconnected-(U3P-NC_75-PadK6)") (class "Default")
      (node (ref "U3") (pin "K6") (pinfunction "NC_75_K6") (pintype "bidirectional"))
    )
    (net (code "110") (name "unconnected-(U3P-NC_76-PadK7)") (class "Default")
      (node (ref "U3") (pin "K7") (pinfunction "NC_76_K7") (pintype "bidirectional"))
    )
  )
)
